# Main.net
KiCad netlist of a schematic drawn in Altium Designer
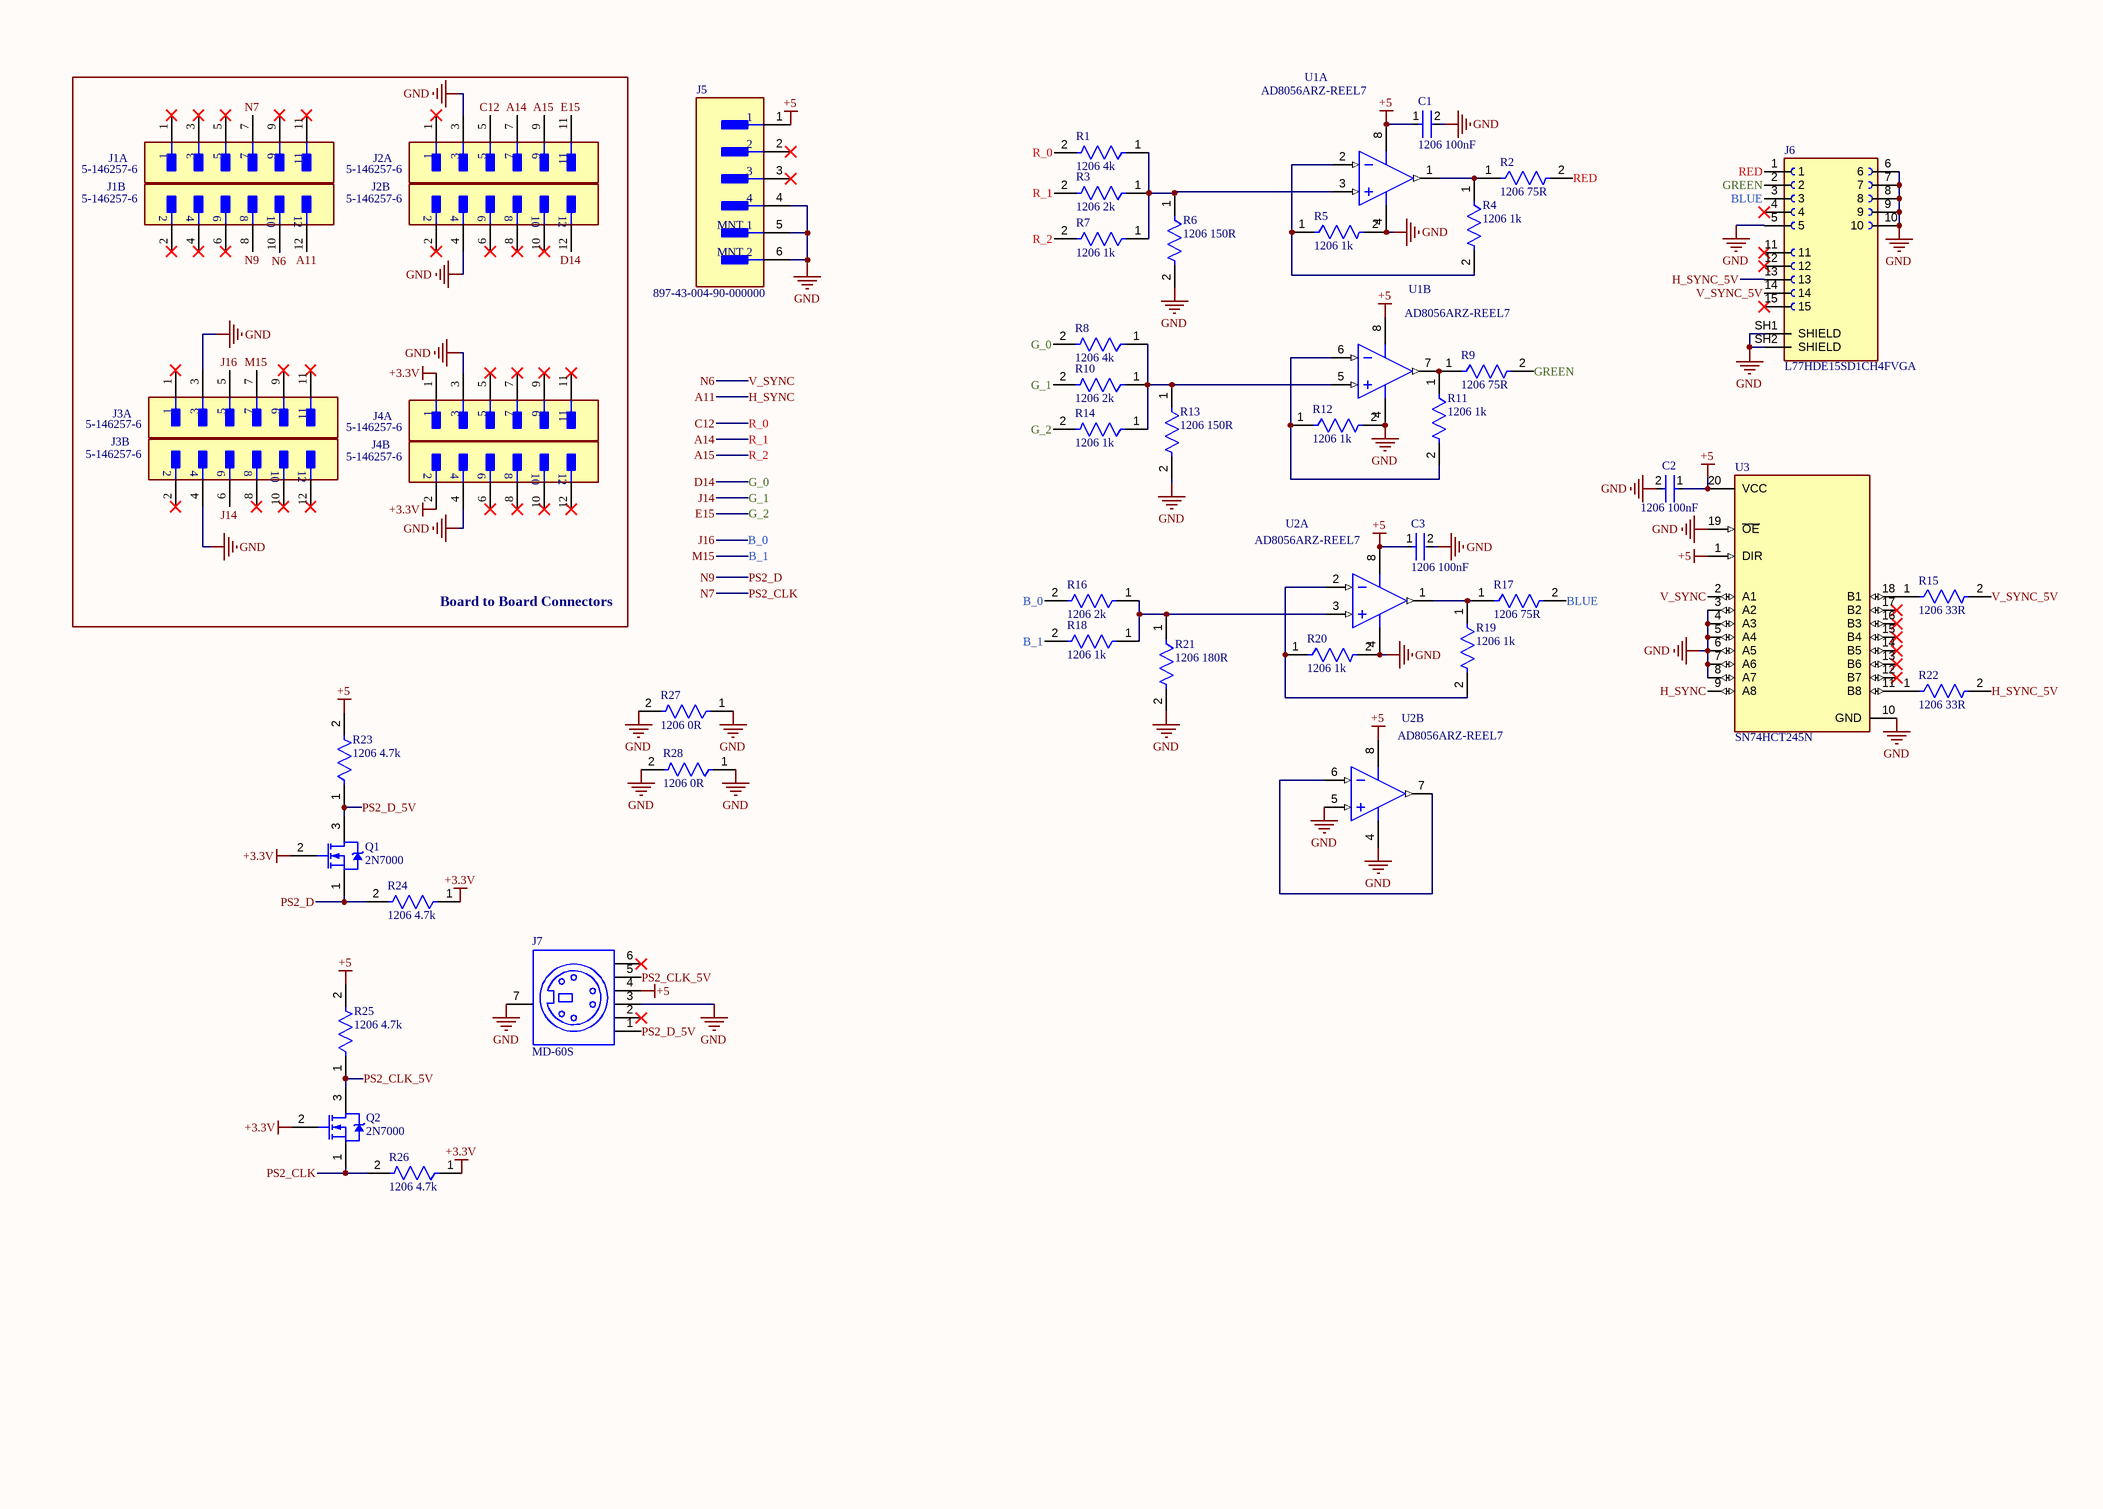
[diagram p0: Main.SchDoc]

(export (version "E")
  (design (tool "Eeschema 10.0.6"))
  (components
    (comp (ref "C1")
      (value "1206 100nF")
      (footprint "FP-1206-L_3_2_0_2-W_1_6_0-MFG")
      (description "Automotive Ceramic Capacitor, 1206, 100nF, 10%, X8R, 15%, 50V")
      (libsource (lib "Altium Content Vault") (part "b4654b650e69147ec39a6b967a45e02"))
    )
    (comp (ref "C2")
      (value "1206 100nF")
      (footprint "FP-1206-L_3_2_0_2-W_1_6_0-MFG")
      (description "Automotive Ceramic Capacitor, 1206, 100nF, 10%, X8R, 15%, 50V")
      (libsource (lib "Altium Content Vault") (part "b4654b650e69147ec39a6b967a45e02"))
    )
    (comp (ref "C3")
      (value "1206 100nF")
      (footprint "FP-1206-L_3_2_0_2-W_1_6_0-MFG")
      (description "Automotive Ceramic Capacitor, 1206, 100nF, 10%, X8R, 15%, 50V")
      (libsource (lib "Altium Content Vault") (part "b4654b650e69147ec39a6b967a45e02"))
    )
    (comp (ref "J1")
      (value "5-146257-6")
      (footprint "FP-5-146257-6-MFG")
      (description "CONN HEADER VERT 12POS 2.54MM")
      (libsource (lib "Altium Content Vault") (part "803cea653fbe7ecf087c1bc3cef566d"))
    )
    (comp (ref "J2")
      (value "5-146257-6")
      (footprint "FP-5-146257-6-MFG")
      (description "CONN HEADER VERT 12POS 2.54MM")
      (libsource (lib "Altium Content Vault") (part "803cea653fbe7ecf087c1bc3cef566d"))
    )
    (comp (ref "J3")
      (value "5-146257-6")
      (footprint "FP-5-146257-6-MFG")
      (description "CONN HEADER VERT 12POS 2.54MM")
      (libsource (lib "") (part "803cea653fbe7ecf087c1bc3cef566d_1"))
    )
    (comp (ref "J4")
      (value "5-146257-6")
      (footprint "FP-5-146257-6-MFG")
      (description "CONN HEADER VERT 12POS 2.54MM")
      (libsource (lib "Altium Content Vault") (part "803cea653fbe7ecf087c1bc3cef566d"))
    )
    (comp (ref "J5")
      (value "897-43-004-90-000000")
      (footprint "FP-897-43-004-90-000000-MFG")
      (description "CONN RCPT USB2.0 TYPEB 4POS R/A")
      (libsource (lib "Altium Content Vault") (part "b418d75d2b00abde1d78e1ec8f4acea"))
    )
    (comp (ref "J6")
      (value "L77HDE15SD1CH4FVGA")
      (footprint "AMPHENOL_L77HDE15SD1CH4FVGA")
      (fields (field (name "MF") "Amphenol Commercial"))
      (libsource (lib "Ebubekir Taşcı") (part "L77HDE15SD1CH4FVGA"))
    )
    (comp (ref "J7")
      (value "MD-60S")
      (footprint "CUI-MD-60S_V")
      (description "Right Angle Mini DIN Connector, 100 Vac, 12 Vdc, -40 to 85 degC, 6-Pin THD, RoHS, Bulk")
      (fields (field (name "MANUFACTURER") "CUI Inc"))
      (libsource (lib "Altium Content Vault") (part "CUI-MD-60S-6"))
    )
    (comp (ref "Q1")
      (value "2N7000")
      (footprint "ONSC-TO-92-3-29-11")
      (description "Small Signal MOSFET, 200 mA, 60 V, N-Channel, 3-Pin TO-92, Bulk Box")
      (fields (field (name "MANUFACTURER") "On Semiconductor"))
      (libsource (lib "Altium Content Vault") (part "ONSC-NMOS-S1G2D3-3"))
    )
    (comp (ref "Q2")
      (value "2N7000")
      (footprint "ONSC-TO-92-3-29-11")
      (description "Small Signal MOSFET, 200 mA, 60 V, N-Channel, 3-Pin TO-92, Bulk Box")
      (fields (field (name "MANUFACTURER") "On Semiconductor"))
      (libsource (lib "Altium Content Vault") (part "ONSC-NMOS-S1G2D3-3"))
    )
    (comp (ref "R1")
      (value "1206 4k")
      (footprint "FP-RMCF1206-MFG")
      (description "1206")
      (fields (field (name "TOLERANCE") "5%"))
      (libsource (lib "Altium Content Vault") (part "1029c3af85768c4190bb7ad29bc67b5"))
    )
    (comp (ref "R2")
      (value "1206 75R")
      (footprint "FP-RMCF1206-MFG")
      (description "1206")
      (fields (field (name "TOLERANCE") "5%"))
      (libsource (lib "Altium Content Vault") (part "1029c3af85768c4190bb7ad29bc67b5"))
    )
    (comp (ref "R3")
      (value "1206 2k")
      (footprint "FP-RMCF1206-MFG")
      (description "1206")
      (fields (field (name "TOLERANCE") "5%"))
      (libsource (lib "Altium Content Vault") (part "1029c3af85768c4190bb7ad29bc67b5"))
    )
    (comp (ref "R4")
      (value "1206 1k")
      (footprint "FP-RMCF1206-MFG")
      (description "1206")
      (fields (field (name "TOLERANCE") "5%"))
      (libsource (lib "Altium Content Vault") (part "1029c3af85768c4190bb7ad29bc67b5"))
    )
    (comp (ref "R5")
      (value "1206 1k")
      (footprint "FP-RMCF1206-MFG")
      (description "1206")
      (fields (field (name "TOLERANCE") "5%"))
      (libsource (lib "Altium Content Vault") (part "1029c3af85768c4190bb7ad29bc67b5"))
    )
    (comp (ref "R6")
      (value "1206 150R")
      (footprint "FP-RMCF1206-MFG")
      (description "1206")
      (fields (field (name "TOLERANCE") "5%"))
      (libsource (lib "Altium Content Vault") (part "1029c3af85768c4190bb7ad29bc67b5"))
    )
    (comp (ref "R7")
      (value "1206 1k")
      (footprint "FP-RMCF1206-MFG")
      (description "1206")
      (fields (field (name "TOLERANCE") "5%"))
      (libsource (lib "Altium Content Vault") (part "1029c3af85768c4190bb7ad29bc67b5"))
    )
    (comp (ref "R8")
      (value "1206 4k")
      (footprint "FP-RMCF1206-MFG")
      (description "1206")
      (fields (field (name "TOLERANCE") "5%"))
      (libsource (lib "Altium Content Vault") (part "1029c3af85768c4190bb7ad29bc67b5"))
    )
    (comp (ref "R9")
      (value "1206 75R")
      (footprint "FP-RMCF1206-MFG")
      (description "1206")
      (fields (field (name "TOLERANCE") "5%"))
      (libsource (lib "Altium Content Vault") (part "1029c3af85768c4190bb7ad29bc67b5"))
    )
    (comp (ref "R10")
      (value "1206 2k")
      (footprint "FP-RMCF1206-MFG")
      (description "1206")
      (fields (field (name "TOLERANCE") "5%"))
      (libsource (lib "Altium Content Vault") (part "1029c3af85768c4190bb7ad29bc67b5"))
    )
    (comp (ref "R11")
      (value "1206 1k")
      (footprint "FP-RMCF1206-MFG")
      (description "1206")
      (fields (field (name "TOLERANCE") "5%"))
      (libsource (lib "Altium Content Vault") (part "1029c3af85768c4190bb7ad29bc67b5"))
    )
    (comp (ref "R12")
      (value "1206 1k")
      (footprint "FP-RMCF1206-MFG")
      (description "1206")
      (fields (field (name "TOLERANCE") "5%"))
      (libsource (lib "Altium Content Vault") (part "1029c3af85768c4190bb7ad29bc67b5"))
    )
    (comp (ref "R13")
      (value "1206 150R")
      (footprint "FP-RMCF1206-MFG")
      (description "1206")
      (fields (field (name "TOLERANCE") "5%"))
      (libsource (lib "Altium Content Vault") (part "1029c3af85768c4190bb7ad29bc67b5"))
    )
    (comp (ref "R14")
      (value "1206 1k")
      (footprint "FP-RMCF1206-MFG")
      (description "1206")
      (fields (field (name "TOLERANCE") "5%"))
      (libsource (lib "Altium Content Vault") (part "1029c3af85768c4190bb7ad29bc67b5"))
    )
    (comp (ref "R15")
      (value "1206 33R")
      (footprint "FP-RMCF1206-MFG")
      (description "1206")
      (fields (field (name "TOLERANCE") "5%"))
      (libsource (lib "Altium Content Vault") (part "1029c3af85768c4190bb7ad29bc67b5"))
    )
    (comp (ref "R16")
      (value "1206 2k")
      (footprint "FP-RMCF1206-MFG")
      (description "1206")
      (fields (field (name "TOLERANCE") "5%"))
      (libsource (lib "Altium Content Vault") (part "1029c3af85768c4190bb7ad29bc67b5"))
    )
    (comp (ref "R17")
      (value "1206 75R")
      (footprint "FP-RMCF1206-MFG")
      (description "1206")
      (fields (field (name "TOLERANCE") "5%"))
      (libsource (lib "Altium Content Vault") (part "1029c3af85768c4190bb7ad29bc67b5"))
    )
    (comp (ref "R18")
      (value "1206 1k")
      (footprint "FP-RMCF1206-MFG")
      (description "1206")
      (fields (field (name "TOLERANCE") "5%"))
      (libsource (lib "Altium Content Vault") (part "1029c3af85768c4190bb7ad29bc67b5"))
    )
    (comp (ref "R19")
      (value "1206 1k")
      (footprint "FP-RMCF1206-MFG")
      (description "1206")
      (fields (field (name "TOLERANCE") "5%"))
      (libsource (lib "Altium Content Vault") (part "1029c3af85768c4190bb7ad29bc67b5"))
    )
    (comp (ref "R20")
      (value "1206 1k")
      (footprint "FP-RMCF1206-MFG")
      (description "1206")
      (fields (field (name "TOLERANCE") "5%"))
      (libsource (lib "Altium Content Vault") (part "1029c3af85768c4190bb7ad29bc67b5"))
    )
    (comp (ref "R21")
      (value "1206 180R")
      (footprint "FP-RMCF1206-MFG")
      (description "1206")
      (fields (field (name "TOLERANCE") "5%"))
      (libsource (lib "Altium Content Vault") (part "1029c3af85768c4190bb7ad29bc67b5"))
    )
    (comp (ref "R22")
      (value "1206 33R")
      (footprint "FP-RMCF1206-MFG")
      (description "1206")
      (fields (field (name "TOLERANCE") "5%"))
      (libsource (lib "Altium Content Vault") (part "1029c3af85768c4190bb7ad29bc67b5"))
    )
    (comp (ref "R23")
      (value "1206 4.7k")
      (footprint "FP-RMCF1206-MFG")
      (description "4.7kΩ ±5% 0.25W 1206 Thick Film Chip Resistor AEC-Q200 compliant")
      (fields (field (name "TOLERANCE") "5%"))
      (libsource (lib "Altium Content Vault") (part "1029c3af85768c4190bb7ad29bc67b5"))
    )
    (comp (ref "R24")
      (value "1206 4.7k")
      (footprint "FP-RMCF1206-MFG")
      (description "4.7kΩ ±5% 0.25W 1206 Thick Film Chip Resistor AEC-Q200 compliant")
      (fields (field (name "TOLERANCE") "5%"))
      (libsource (lib "Altium Content Vault") (part "1029c3af85768c4190bb7ad29bc67b5"))
    )
    (comp (ref "R25")
      (value "1206 4.7k")
      (footprint "FP-RMCF1206-MFG")
      (description "4.7kΩ ±5% 0.25W 1206 Thick Film Chip Resistor AEC-Q200 compliant")
      (fields (field (name "TOLERANCE") "5%"))
      (libsource (lib "Altium Content Vault") (part "1029c3af85768c4190bb7ad29bc67b5"))
    )
    (comp (ref "R26")
      (value "1206 4.7k")
      (footprint "FP-RMCF1206-MFG")
      (description "4.7kΩ ±5% 0.25W 1206 Thick Film Chip Resistor AEC-Q200 compliant")
      (fields (field (name "TOLERANCE") "5%"))
      (libsource (lib "Altium Content Vault") (part "1029c3af85768c4190bb7ad29bc67b5"))
    )
    (comp (ref "R27")
      (value "1206 0R")
      (footprint "FP-RMCF1206-MFG")
      (description "1206")
      (fields (field (name "TOLERANCE") "5%"))
      (libsource (lib "Altium Content Vault") (part "1029c3af85768c4190bb7ad29bc67b5"))
    )
    (comp (ref "R28")
      (value "1206 0R")
      (footprint "FP-RMCF1206-MFG")
      (description "1206")
      (fields (field (name "TOLERANCE") "5%"))
      (libsource (lib "Altium Content Vault") (part "1029c3af85768c4190bb7ad29bc67b5"))
    )
    (comp (ref "U1")
      (value "AD8056ARZ-REEL7")
      (footprint "ADI-R-8_M")
      (fields (field (name "GENERIC PART NUMBER") "AD8056") (field (name "MANUFACTURER") "Analog Devices"))
      (libsource (lib "Altium Content Vault") (part "ADI-AD80XX-8"))
    )
    (comp (ref "U2")
      (value "AD8056ARZ-REEL7")
      (footprint "ADI-R-8_M")
      (fields (field (name "GENERIC PART NUMBER") "AD8056") (field (name "MANUFACTURER") "Analog Devices"))
      (libsource (lib "Altium Content Vault") (part "ADI-AD80XX-8"))
    )
    (comp (ref "U3")
      (value "SN74HCT245N")
      (footprint "FP-SN74HCT245N-MFG")
      (description "IC TXRX NON-INVERT 5.5V 20DIP")
      (fields
        (field (name "OCTOPART") "https://octopart.com/sn74hct245n-texas+instruments-517043")
        (field (name "MANUFACTURER") "Texas Instruments")
      )
      (libsource (lib "Altium Content Vault") (part "bb5d13c93c6235e9fb9735f3d1d6aac"))
    )
  )
  (nets
    (net (code "1") (name "+3.3V") (class "Default")
      (node (ref "J4") (pin "1") (pinfunction "1_1") (pintype "passive"))
      (node (ref "J4") (pin "2") (pinfunction "2_2") (pintype "passive"))
      (node (ref "Q1") (pin "2") (pinfunction "G_2") (pintype "passive"))
      (node (ref "Q2") (pin "2") (pinfunction "G_2") (pintype "passive"))
      (node (ref "R24") (pin "1") (pinfunction "1_1") (pintype "passive"))
      (node (ref "R26") (pin "1") (pinfunction "1_1") (pintype "passive"))
    )
    (net (code "2") (name "+5") (class "Default")
      (node (ref "C1") (pin "1") (pinfunction "1_1") (pintype "passive"))
      (node (ref "C2") (pin "1") (pinfunction "1_1") (pintype "passive"))
      (node (ref "C3") (pin "1") (pinfunction "1_1") (pintype "passive"))
      (node (ref "J5") (pin "1") (pinfunction "1_1") (pintype "passive"))
      (node (ref "J7") (pin "4") (pinfunction "4_4") (pintype "passive"))
      (node (ref "R23") (pin "2") (pinfunction "2_2") (pintype "passive"))
      (node (ref "R25") (pin "2") (pinfunction "2_2") (pintype "passive"))
      (node (ref "U1") (pin "8") (pinfunction "+VS_8") (pintype "power_in"))
      (node (ref "U2") (pin "8") (pinfunction "+VS_8") (pintype "power_in"))
      (node (ref "U3") (pin "1") (pinfunction "DIR_1") (pintype "input"))
      (node (ref "U3") (pin "20") (pinfunction "VCC_20") (pintype "power_in"))
    )
    (net (code "3") (name "/A11") (class "Default")
      (node (ref "J1") (pin "12") (pinfunction "12_12") (pintype "passive"))
      (node (ref "U3") (pin "9") (pinfunction "A8_9") (pintype "bidirectional"))
    )
    (net (code "4") (name "/A14") (class "Default")
      (node (ref "J2") (pin "7") (pinfunction "7_7") (pintype "passive"))
      (node (ref "R3") (pin "2") (pinfunction "2_2") (pintype "passive"))
    )
    (net (code "5") (name "/A15") (class "Default")
      (node (ref "J2") (pin "9") (pinfunction "9_9") (pintype "passive"))
      (node (ref "R7") (pin "2") (pinfunction "2_2") (pintype "passive"))
    )
    (net (code "6") (name "/BLUE") (class "Default")
      (node (ref "J6") (pin "3") (pinfunction "3_3") (pintype "passive"))
      (node (ref "R17") (pin "2") (pinfunction "2_2") (pintype "passive"))
    )
    (net (code "7") (name "/B_0") (class "Default")
      (node (ref "J3") (pin "5") (pinfunction "5_5") (pintype "passive"))
      (node (ref "R16") (pin "2") (pinfunction "2_2") (pintype "passive"))
    )
    (net (code "8") (name "/B_1") (class "Default")
      (node (ref "J3") (pin "7") (pinfunction "7_7") (pintype "passive"))
      (node (ref "R18") (pin "2") (pinfunction "2_2") (pintype "passive"))
    )
    (net (code "9") (name "/C12") (class "Default")
      (node (ref "J2") (pin "5") (pinfunction "5_5") (pintype "passive"))
      (node (ref "R1") (pin "2") (pinfunction "2_2") (pintype "passive"))
    )
    (net (code "10") (name "/D14") (class "Default")
      (node (ref "J2") (pin "12") (pinfunction "12_12") (pintype "passive"))
      (node (ref "R8") (pin "2") (pinfunction "2_2") (pintype "passive"))
    )
    (net (code "11") (name "/E15") (class "Default")
      (node (ref "J2") (pin "11") (pinfunction "11_11") (pintype "passive"))
      (node (ref "R14") (pin "2") (pinfunction "2_2") (pintype "passive"))
    )
    (net (code "12") (name "/GREEN") (class "Default")
      (node (ref "J6") (pin "2") (pinfunction "2_2") (pintype "passive"))
      (node (ref "R9") (pin "2") (pinfunction "2_2") (pintype "passive"))
    )
    (net (code "13") (name "/G_1") (class "Default")
      (node (ref "J3") (pin "6") (pinfunction "6_6") (pintype "passive"))
      (node (ref "R10") (pin "2") (pinfunction "2_2") (pintype "passive"))
    )
    (net (code "14") (name "/H_SYNC_5V") (class "Default")
      (node (ref "J6") (pin "13") (pinfunction "13_13") (pintype "passive"))
      (node (ref "R22") (pin "2") (pinfunction "2_2") (pintype "passive"))
    )
    (net (code "15") (name "/N6") (class "Default")
      (node (ref "J1") (pin "10") (pinfunction "10_10") (pintype "passive"))
      (node (ref "U3") (pin "2") (pinfunction "A1_2") (pintype "bidirectional"))
    )
    (net (code "16") (name "/N7") (class "Default")
      (node (ref "J1") (pin "7") (pinfunction "7_7") (pintype "passive"))
      (node (ref "Q2") (pin "1") (pinfunction "S_1") (pintype "passive"))
      (node (ref "R26") (pin "2") (pinfunction "2_2") (pintype "passive"))
    )
    (net (code "17") (name "/N9") (class "Default")
      (node (ref "J1") (pin "8") (pinfunction "8_8") (pintype "passive"))
      (node (ref "Q1") (pin "1") (pinfunction "S_1") (pintype "passive"))
      (node (ref "R24") (pin "2") (pinfunction "2_2") (pintype "passive"))
    )
    (net (code "18") (name "/PS2_CLK_5V") (class "Default")
      (node (ref "J7") (pin "5") (pinfunction "5_5") (pintype "passive"))
      (node (ref "Q2") (pin "3") (pinfunction "D_3") (pintype "passive"))
      (node (ref "R25") (pin "1") (pinfunction "1_1") (pintype "passive"))
    )
    (net (code "19") (name "/PS2_D_5V") (class "Default")
      (node (ref "J7") (pin "1") (pinfunction "1_1") (pintype "passive"))
      (node (ref "Q1") (pin "3") (pinfunction "D_3") (pintype "passive"))
      (node (ref "R23") (pin "1") (pinfunction "1_1") (pintype "passive"))
    )
    (net (code "20") (name "/RED") (class "Default")
      (node (ref "J6") (pin "1") (pinfunction "1_1") (pintype "passive"))
      (node (ref "R2") (pin "2") (pinfunction "2_2") (pintype "passive"))
    )
    (net (code "21") (name "/V_SYNC_5V") (class "Default")
      (node (ref "J6") (pin "14") (pinfunction "14_14") (pintype "passive"))
      (node (ref "R15") (pin "2") (pinfunction "2_2") (pintype "passive"))
    )
    (net (code "22") (name "GND") (class "Default")
      (node (ref "C1") (pin "2") (pinfunction "2_2") (pintype "passive"))
      (node (ref "C2") (pin "2") (pinfunction "2_2") (pintype "passive"))
      (node (ref "C3") (pin "2") (pinfunction "2_2") (pintype "passive"))
      (node (ref "J2") (pin "3") (pinfunction "3_3") (pintype "passive"))
      (node (ref "J2") (pin "4") (pinfunction "4_4") (pintype "passive"))
      (node (ref "J3") (pin "3") (pinfunction "3_3") (pintype "passive"))
      (node (ref "J3") (pin "4") (pinfunction "4_4") (pintype "passive"))
      (node (ref "J4") (pin "3") (pinfunction "3_3") (pintype "passive"))
      (node (ref "J4") (pin "4") (pinfunction "4_4") (pintype "passive"))
      (node (ref "J5") (pin "4") (pinfunction "4_4") (pintype "passive"))
      (node (ref "J5") (pin "5") (pinfunction "MNT_1_5") (pintype "passive"))
      (node (ref "J5") (pin "6") (pinfunction "MNT_2_6") (pintype "passive"))
      (node (ref "J6") (pin "10") (pinfunction "10_10") (pintype "passive"))
      (node (ref "J6") (pin "5") (pinfunction "5_5") (pintype "passive"))
      (node (ref "J6") (pin "6") (pinfunction "6_6") (pintype "passive"))
      (node (ref "J6") (pin "7") (pinfunction "7_7") (pintype "passive"))
      (node (ref "J6") (pin "8") (pinfunction "8_8") (pintype "passive"))
      (node (ref "J6") (pin "9") (pinfunction "9_9") (pintype "passive"))
      (node (ref "J6") (pin "SH1") (pinfunction "SHIELD_SH1") (pintype "passive"))
      (node (ref "J6") (pin "SH2") (pinfunction "SHIELD_SH2") (pintype "passive"))
      (node (ref "J7") (pin "3") (pinfunction "3_3") (pintype "passive"))
      (node (ref "J7") (pin "7") (pinfunction "7_7") (pintype "passive"))
      (node (ref "R12") (pin "2") (pinfunction "2_2") (pintype "passive"))
      (node (ref "R13") (pin "2") (pinfunction "2_2") (pintype "passive"))
      (node (ref "R20") (pin "2") (pinfunction "2_2") (pintype "passive"))
      (node (ref "R21") (pin "2") (pinfunction "2_2") (pintype "passive"))
      (node (ref "R27") (pin "1") (pinfunction "1_1") (pintype "passive"))
      (node (ref "R27") (pin "2") (pinfunction "2_2") (pintype "passive"))
      (node (ref "R28") (pin "1") (pinfunction "1_1") (pintype "passive"))
      (node (ref "R28") (pin "2") (pinfunction "2_2") (pintype "passive"))
      (node (ref "R5") (pin "2") (pinfunction "2_2") (pintype "passive"))
      (node (ref "R6") (pin "2") (pinfunction "2_2") (pintype "passive"))
      (node (ref "U1") (pin "4") (pinfunction "-VS_4") (pintype "power_in"))
      (node (ref "U2") (pin "4") (pinfunction "-VS_4") (pintype "power_in"))
      (node (ref "U2") (pin "5") (pinfunction "+IN_2_5") (pintype "input"))
      (node (ref "U3") (pin "10") (pinfunction "GND_10") (pintype "power_in"))
      (node (ref "U3") (pin "19") (pinfunction "~{OE}_19") (pintype "input"))
      (node (ref "U3") (pin "3") (pinfunction "A2_3") (pintype "bidirectional"))
      (node (ref "U3") (pin "4") (pinfunction "A3_4") (pintype "bidirectional"))
      (node (ref "U3") (pin "5") (pinfunction "A4_5") (pintype "bidirectional"))
      (node (ref "U3") (pin "6") (pinfunction "A5_6") (pintype "bidirectional"))
      (node (ref "U3") (pin "7") (pinfunction "A6_7") (pintype "bidirectional"))
      (node (ref "U3") (pin "8") (pinfunction "A7_8") (pintype "bidirectional"))
    )
    (net (code "23") (name "Net-(U1A-+IN_1)") (class "Default")
      (node (ref "R1") (pin "1") (pinfunction "1_1") (pintype "passive"))
      (node (ref "R3") (pin "1") (pinfunction "1_1") (pintype "passive"))
      (node (ref "R6") (pin "1") (pinfunction "1_1") (pintype "passive"))
      (node (ref "R7") (pin "1") (pinfunction "1_1") (pintype "passive"))
      (node (ref "U1") (pin "3") (pinfunction "+IN_1_3") (pintype "input"))
    )
    (net (code "24") (name "Net-(U1A--IN_1)") (class "Default")
      (node (ref "R4") (pin "2") (pinfunction "2_2") (pintype "passive"))
      (node (ref "R5") (pin "1") (pinfunction "1_1") (pintype "passive"))
      (node (ref "U1") (pin "2") (pinfunction "-IN_1_2") (pintype "input"))
    )
    (net (code "25") (name "Net-(U1A-OUT_1)") (class "Default")
      (node (ref "R2") (pin "1") (pinfunction "1_1") (pintype "passive"))
      (node (ref "R4") (pin "1") (pinfunction "1_1") (pintype "passive"))
      (node (ref "U1") (pin "1") (pinfunction "OUT_1_1") (pintype "output"))
    )
    (net (code "26") (name "Net-(U1B-+IN_2)") (class "Default")
      (node (ref "R10") (pin "1") (pinfunction "1_1") (pintype "passive"))
      (node (ref "R13") (pin "1") (pinfunction "1_1") (pintype "passive"))
      (node (ref "R14") (pin "1") (pinfunction "1_1") (pintype "passive"))
      (node (ref "R8") (pin "1") (pinfunction "1_1") (pintype "passive"))
      (node (ref "U1") (pin "5") (pinfunction "+IN_2_5") (pintype "input"))
    )
    (net (code "27") (name "Net-(U1B--IN_2)") (class "Default")
      (node (ref "R11") (pin "2") (pinfunction "2_2") (pintype "passive"))
      (node (ref "R12") (pin "1") (pinfunction "1_1") (pintype "passive"))
      (node (ref "U1") (pin "6") (pinfunction "-IN_2_6") (pintype "input"))
    )
    (net (code "28") (name "Net-(U1B-OUT_2)") (class "Default")
      (node (ref "R11") (pin "1") (pinfunction "1_1") (pintype "passive"))
      (node (ref "R9") (pin "1") (pinfunction "1_1") (pintype "passive"))
      (node (ref "U1") (pin "7") (pinfunction "OUT_2_7") (pintype "output"))
    )
    (net (code "29") (name "Net-(U2A-+IN_1)") (class "Default")
      (node (ref "R16") (pin "1") (pinfunction "1_1") (pintype "passive"))
      (node (ref "R18") (pin "1") (pinfunction "1_1") (pintype "passive"))
      (node (ref "R21") (pin "1") (pinfunction "1_1") (pintype "passive"))
      (node (ref "U2") (pin "3") (pinfunction "+IN_1_3") (pintype "input"))
    )
    (net (code "30") (name "Net-(U2A--IN_1)") (class "Default")
      (node (ref "R19") (pin "2") (pinfunction "2_2") (pintype "passive"))
      (node (ref "R20") (pin "1") (pinfunction "1_1") (pintype "passive"))
      (node (ref "U2") (pin "2") (pinfunction "-IN_1_2") (pintype "input"))
    )
    (net (code "31") (name "Net-(U2A-OUT_1)") (class "Default")
      (node (ref "R17") (pin "1") (pinfunction "1_1") (pintype "passive"))
      (node (ref "R19") (pin "1") (pinfunction "1_1") (pintype "passive"))
      (node (ref "U2") (pin "1") (pinfunction "OUT_1_1") (pintype "output"))
    )
    (net (code "32") (name "Net-(U2B--IN_2)") (class "Default")
      (node (ref "U2") (pin "6") (pinfunction "-IN_2_6") (pintype "input"))
      (node (ref "U2") (pin "7") (pinfunction "OUT_2_7") (pintype "output"))
    )
    (net (code "33") (name "Net-(U3-B1)") (class "Default")
      (node (ref "R15") (pin "1") (pinfunction "1_1") (pintype "passive"))
      (node (ref "U3") (pin "18") (pinfunction "B1_18") (pintype "bidirectional"))
    )
    (net (code "34") (name "Net-(U3-B8)") (class "Default")
      (node (ref "R22") (pin "1") (pinfunction "1_1") (pintype "passive"))
      (node (ref "U3") (pin "11") (pinfunction "B8_11") (pintype "bidirectional"))
    )
    (net (code "35") (name "unconnected-(J1-Pad1)") (class "Default")
      (node (ref "J1") (pin "1") (pinfunction "1_1") (pintype "passive+no_connect"))
    )
    (net (code "36") (name "unconnected-(J1-Pad2)") (class "Default")
      (node (ref "J1") (pin "2") (pinfunction "2_2") (pintype "passive+no_connect"))
    )
    (net (code "37") (name "unconnected-(J1-Pad3)") (class "Default")
      (node (ref "J1") (pin "3") (pinfunction "3_3") (pintype "passive+no_connect"))
    )
    (net (code "38") (name "unconnected-(J1-Pad4)") (class "Default")
      (node (ref "J1") (pin "4") (pinfunction "4_4") (pintype "passive+no_connect"))
    )
    (net (code "39") (name "unconnected-(J1-Pad5)") (class "Default")
      (node (ref "J1") (pin "5") (pinfunction "5_5") (pintype "passive+no_connect"))
    )
    (net (code "40") (name "unconnected-(J1-Pad6)") (class "Default")
      (node (ref "J1") (pin "6") (pinfunction "6_6") (pintype "passive+no_connect"))
    )
    (net (code "41") (name "unconnected-(J1-Pad9)") (class "Default")
      (node (ref "J1") (pin "9") (pinfunction "9_9") (pintype "passive+no_connect"))
    )
    (net (code "42") (name "unconnected-(J1-Pad11)") (class "Default")
      (node (ref "J1") (pin "11") (pinfunction "11_11") (pintype "passive+no_connect"))
    )
    (net (code "43") (name "unconnected-(J2-Pad1)") (class "Default")
      (node (ref "J2") (pin "1") (pinfunction "1_1") (pintype "passive+no_connect"))
    )
    (net (code "44") (name "unconnected-(J2-Pad2)") (class "Default")
      (node (ref "J2") (pin "2") (pinfunction "2_2") (pintype "passive+no_connect"))
    )
    (net (code "45") (name "unconnected-(J2-Pad6)") (class "Default")
      (node (ref "J2") (pin "6") (pinfunction "6_6") (pintype "passive+no_connect"))
    )
    (net (code "46") (name "unconnected-(J2-Pad8)") (class "Default")
      (node (ref "J2") (pin "8") (pinfunction "8_8") (pintype "passive+no_connect"))
    )
    (net (code "47") (name "unconnected-(J2-Pad10)") (class "Default")
      (node (ref "J2") (pin "10") (pinfunction "10_10") (pintype "passive+no_connect"))
    )
    (net (code "48") (name "unconnected-(J3-Pad1)") (class "Default")
      (node (ref "J3") (pin "1") (pinfunction "1_1") (pintype "passive+no_connect"))
    )
    (net (code "49") (name "unconnected-(J3-Pad2)") (class "Default")
      (node (ref "J3") (pin "2") (pinfunction "2_2") (pintype "passive+no_connect"))
    )
    (net (code "50") (name "unconnected-(J3-Pad8)") (class "Default")
      (node (ref "J3") (pin "8") (pinfunction "8_8") (pintype "passive+no_connect"))
    )
    (net (code "51") (name "unconnected-(J3-Pad9)") (class "Default")
      (node (ref "J3") (pin "9") (pinfunction "9_9") (pintype "passive+no_connect"))
    )
    (net (code "52") (name "unconnected-(J3-Pad10)") (class "Default")
      (node (ref "J3") (pin "10") (pinfunction "10_10") (pintype "passive+no_connect"))
    )
    (net (code "53") (name "unconnected-(J3-Pad11)") (class "Default")
      (node (ref "J3") (pin "11") (pinfunction "11_11") (pintype "passive+no_connect"))
    )
    (net (code "54") (name "unconnected-(J3-Pad12)") (class "Default")
      (node (ref "J3") (pin "12") (pinfunction "12_12") (pintype "passive+no_connect"))
    )
    (net (code "55") (name "unconnected-(J4-Pad5)") (class "Default")
      (node (ref "J4") (pin "5") (pinfunction "5_5") (pintype "passive+no_connect"))
    )
    (net (code "56") (name "unconnected-(J4-Pad6)") (class "Default")
      (node (ref "J4") (pin "6") (pinfunction "6_6") (pintype "passive+no_connect"))
    )
    (net (code "57") (name "unconnected-(J4-Pad7)") (class "Default")
      (node (ref "J4") (pin "7") (pinfunction "7_7") (pintype "passive+no_connect"))
    )
    (net (code "58") (name "unconnected-(J4-Pad8)") (class "Default")
      (node (ref "J4") (pin "8") (pinfunction "8_8") (pintype "passive+no_connect"))
    )
    (net (code "59") (name "unconnected-(J4-Pad9)") (class "Default")
      (node (ref "J4") (pin "9") (pinfunction "9_9") (pintype "passive+no_connect"))
    )
    (net (code "60") (name "unconnected-(J4-Pad10)") (class "Default")
      (node (ref "J4") (pin "10") (pinfunction "10_10") (pintype "passive+no_connect"))
    )
    (net (code "61") (name "unconnected-(J4-Pad11)") (class "Default")
      (node (ref "J4") (pin "11") (pinfunction "11_11") (pintype "passive+no_connect"))
    )
    (net (code "62") (name "unconnected-(J4-Pad12)") (class "Default")
      (node (ref "J4") (pin "12") (pinfunction "12_12") (pintype "passive+no_connect"))
    )
    (net (code "63") (name "unconnected-(J5-Pad2)") (class "Default")
      (node (ref "J5") (pin "2") (pinfunction "2_2") (pintype "passive+no_connect"))
    )
    (net (code "64") (name "unconnected-(J5-Pad3)") (class "Default")
      (node (ref "J5") (pin "3") (pinfunction "3_3") (pintype "passive+no_connect"))
    )
    (net (code "65") (name "unconnected-(J6-Pad4)") (class "Default")
      (node (ref "J6") (pin "4") (pinfunction "4_4") (pintype "passive+no_connect"))
    )
    (net (code "66") (name "unconnected-(J6-Pad11)") (class "Default")
      (node (ref "J6") (pin "11") (pinfunction "11_11") (pintype "passive+no_connect"))
    )
    (net (code "67") (name "unconnected-(J6-Pad12)") (class "Default")
      (node (ref "J6") (pin "12") (pinfunction "12_12") (pintype "passive+no_connect"))
    )
    (net (code "68") (name "unconnected-(J6-Pad15)") (class "Default")
      (node (ref "J6") (pin "15") (pinfunction "15_15") (pintype "passive+no_connect"))
    )
    (net (code "69") (name "unconnected-(J7-Pad2)") (class "Default")
      (node (ref "J7") (pin "2") (pinfunction "2_2") (pintype "passive+no_connect"))
    )
    (net (code "70") (name "unconnected-(J7-Pad6)") (class "Default")
      (node (ref "J7") (pin "6") (pinfunction "6_6") (pintype "passive+no_connect"))
    )
    (net (code "71") (name "unconnected-(U3-B2-Pad17)") (class "Default")
      (node (ref "U3") (pin "17") (pinfunction "B2_17") (pintype "bidirectional+no_connect"))
    )
    (net (code "72") (name "unconnected-(U3-B3-Pad16)") (class "Default")
      (node (ref "U3") (pin "16") (pinfunction "B3_16") (pintype "bidirectional+no_connect"))
    )
    (net (code "73") (name "unconnected-(U3-B4-Pad15)") (class "Default")
      (node (ref "U3") (pin "15") (pinfunction "B4_15") (pintype "bidirectional+no_connect"))
    )
    (net (code "74") (name "unconnected-(U3-B5-Pad14)") (class "Default")
      (node (ref "U3") (pin "14") (pinfunction "B5_14") (pintype "bidirectional+no_connect"))
    )
    (net (code "75") (name "unconnected-(U3-B6-Pad13)") (class "Default")
      (node (ref "U3") (pin "13") (pinfunction "B6_13") (pintype "bidirectional+no_connect"))
    )
    (net (code "76") (name "unconnected-(U3-B7-Pad12)") (class "Default")
      (node (ref "U3") (pin "12") (pinfunction "B7_12") (pintype "bidirectional+no_connect"))
    )
  )
)
